# custom_schematic.net
KiCad netlist of a schematic drawn in EAGLE
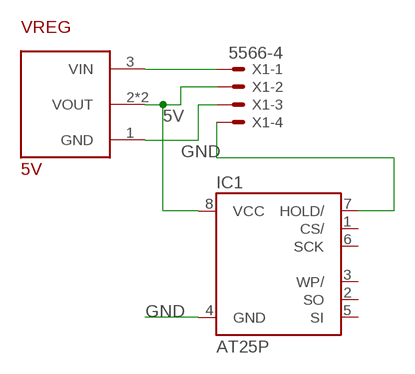
[diagram p0: schematic, sheet 1]

(export (version "E")
  (design (tool "Eeschema 10.0.6"))
  (components
    (comp (ref "IC1")
      (value "AT25P")
      (footprint "eagle-import:DIL08")
      (fields (field (name "MPN") "CAT25040LI-G"))
      (libsource (lib "eagle-import") (part "AT25P"))
    )
    (comp (ref "VREG")
      (value "5V")
      (footprint "eagle-import:VOLTAGE-REGULATOR")
      (libsource (lib "eagle-import") (part "VOLTAGE-REGULATOR"))
    )
    (comp (ref "X1")
      (value "5566-4")
      (footprint "eagle-import:5566-4")
      (fields (field (name "MF") "MOLEX"))
      (libsource (lib "eagle-import") (part "5566-4"))
    )
  )
  (nets
    (net (code "1") (name "/5V") (class "Default")
      (node (ref "IC1") (pin "8") (pinfunction "VCC_8") (pintype "power_in"))
      (node (ref "VREG") (pin "2") (pinfunction "VOUT_2") (pintype "bidirectional"))
      (node (ref "VREG") (pin "2B") (pinfunction "VOUT_2B") (pintype "bidirectional"))
      (node (ref "X1") (pin "2") (pinfunction "S_2") (pintype "passive"))
    )
    (net (code "2") (name "/GND") (class "Default")
      (node (ref "IC1") (pin "4") (pinfunction "GND_4") (pintype "power_in"))
      (node (ref "VREG") (pin "1") (pinfunction "GND_1") (pintype "bidirectional"))
      (node (ref "X1") (pin "3") (pinfunction "S_3") (pintype "passive"))
    )
    (net (code "3") (name "Net-(IC1-HOLD{slash})") (class "Default")
      (node (ref "IC1") (pin "7") (pinfunction "HOLD/_7") (pintype "input"))
      (node (ref "X1") (pin "4") (pinfunction "S_4") (pintype "passive"))
    )
    (net (code "4") (name "Net-(VREG-VIN)") (class "Default")
      (node (ref "VREG") (pin "3") (pinfunction "VIN_3") (pintype "bidirectional"))
      (node (ref "X1") (pin "1") (pinfunction "S_1") (pintype "passive"))
    )
    (net (code "5") (name "unconnected-(IC1-CS{slash}-Pad1)") (class "Default")
      (node (ref "IC1") (pin "1") (pinfunction "CS/_1") (pintype "input"))
    )
    (net (code "6") (name "unconnected-(IC1-SCK-Pad6)") (class "Default")
      (node (ref "IC1") (pin "6") (pinfunction "SCK_6") (pintype "bidirectional"))
    )
    (net (code "7") (name "unconnected-(IC1-SI-Pad5)") (class "Default")
      (node (ref "IC1") (pin "5") (pinfunction "SI_5") (pintype "bidirectional"))
    )
    (net (code "8") (name "unconnected-(IC1-SO-Pad2)") (class "Default")
      (node (ref "IC1") (pin "2") (pinfunction "SO_2") (pintype "input"))
    )
    (net (code "9") (name "unconnected-(IC1-WP{slash}-Pad3)") (class "Default")
      (node (ref "IC1") (pin "3") (pinfunction "WP/_3") (pintype "input"))
    )
  )
)
